# 32a4u.net
KiCad netlist of a schematic drawn in EAGLE
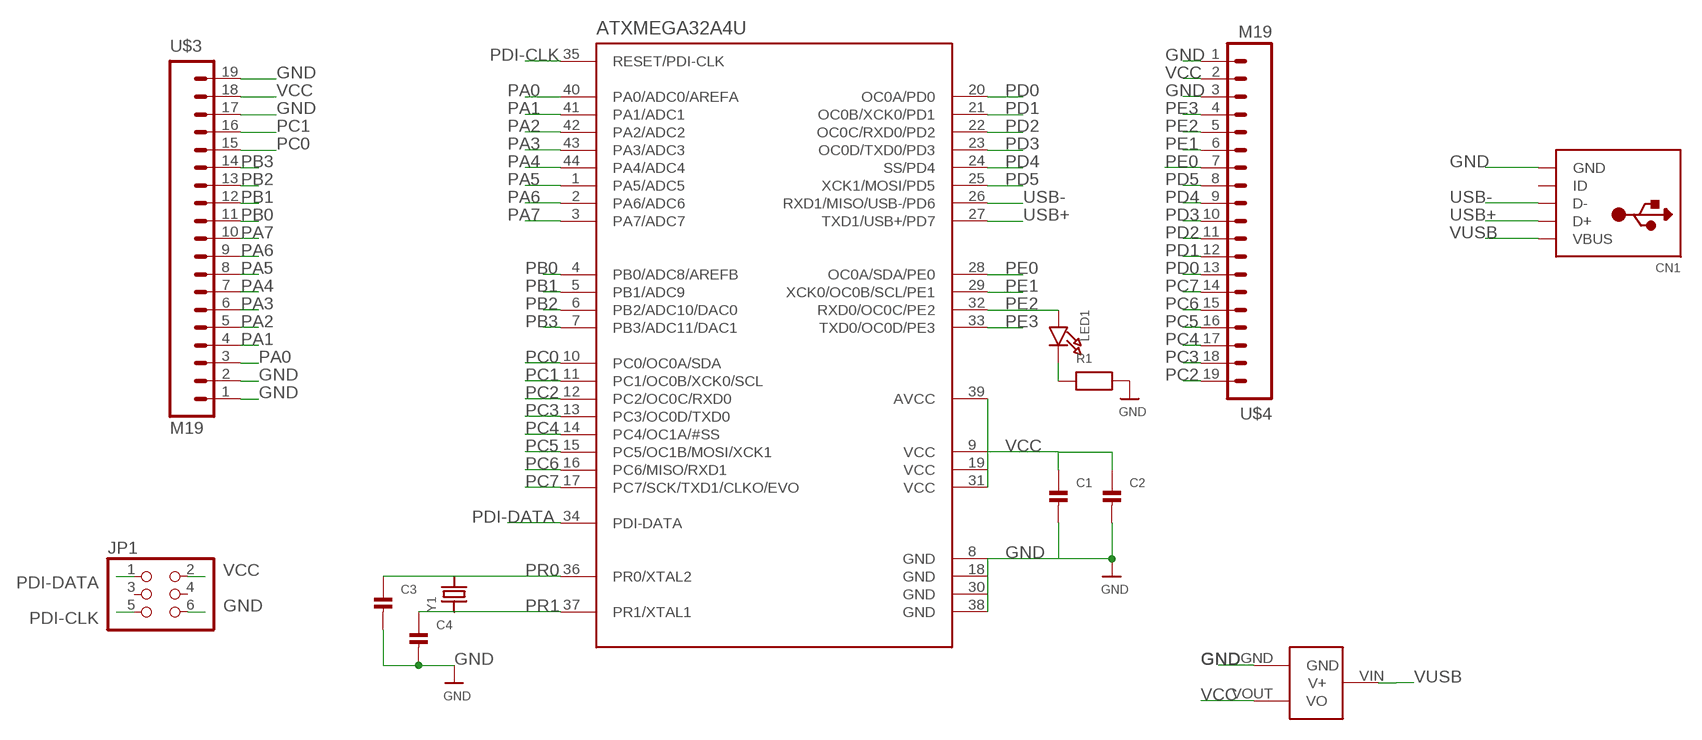
[diagram p0: schematic, sheet 1]

(export (version "E")
  (design (tool "Eeschema 10.0.6"))
  (components
    (comp (ref "ATXMEGA32A4U")
      (value "ATXMEGAXXA4U-AU")
      (footprint "eagle-import:TQFP-44")
      (libsource (lib "eagle-import") (part "ATXMEGAXXA4U-AU"))
    )
    (comp (ref "C1")
      (value "CAP_CERAMIC0603")
      (footprint "eagle-import:0603")
      (libsource (lib "eagle-import") (part "CAP_CERAMIC0603"))
    )
    (comp (ref "C2")
      (value "CAP_CERAMIC0603")
      (footprint "eagle-import:0603")
      (libsource (lib "eagle-import") (part "CAP_CERAMIC0603"))
    )
    (comp (ref "C3")
      (value "CAP_CERAMIC0603")
      (footprint "eagle-import:0603")
      (libsource (lib "eagle-import") (part "CAP_CERAMIC0603"))
    )
    (comp (ref "C4")
      (value "CAP_CERAMIC0603")
      (footprint "eagle-import:0603")
      (libsource (lib "eagle-import") (part "CAP_CERAMIC0603"))
    )
    (comp (ref "CN1")
      (value "USBMICROB")
      (footprint "eagle-import:USB-MICROB")
      (libsource (lib "eagle-import") (part "USBMICROB"))
    )
    (comp (ref "JP1")
      (value "HEADER-2X3")
      (footprint "eagle-import:2X03")
      (libsource (lib "eagle-import") (part "HEADER-2X3"))
    )
    (comp (ref "LED1")
      (value "LED0603")
      (footprint "eagle-import:CHIPLED_0603")
      (libsource (lib "eagle-import") (part "LED0603"))
    )
    (comp (ref "R1")
      (value "RESISTOR0603")
      (footprint "eagle-import:0603")
      (libsource (lib "eagle-import") (part "RESISTOR0603"))
    )
    (comp (ref "U$2")
      (value "MCP1700")
      (footprint "eagle-import:SOT23-3")
      (libsource (lib "eagle-import") (part "MCP1700"))
    )
    (comp (ref "U$3")
      (value "M19")
      (footprint "eagle-import:1X19")
      (libsource (lib "eagle-import") (part "M19"))
    )
    (comp (ref "U$4")
      (value "M19")
      (footprint "eagle-import:1X19")
      (libsource (lib "eagle-import") (part "M19"))
    )
    (comp (ref "Y1")
      (value "CRYSTAL")
      (footprint "eagle-import:NX8045GB")
      (libsource (lib "eagle-import") (part "CRYSTAL"))
    )
  )
  (nets
    (net (code "1") (name "/PA0") (class "Default")
      (node (ref "ATXMEGA32A4U") (pin "40") (pinfunction "PA0/ADC0/AREFA_40") (pintype "bidirectional"))
      (node (ref "U$3") (pin "3") (pinfunction "3_3") (pintype "passive"))
    )
    (net (code "2") (name "/PA1") (class "Default")
      (node (ref "ATXMEGA32A4U") (pin "41") (pinfunction "PA1/ADC1_41") (pintype "bidirectional"))
      (node (ref "U$3") (pin "4") (pinfunction "4_4") (pintype "passive"))
    )
    (net (code "3") (name "/PA2") (class "Default")
      (node (ref "ATXMEGA32A4U") (pin "42") (pinfunction "PA2/ADC2_42") (pintype "bidirectional"))
      (node (ref "U$3") (pin "5") (pinfunction "5_5") (pintype "passive"))
    )
    (net (code "4") (name "/PA3") (class "Default")
      (node (ref "ATXMEGA32A4U") (pin "43") (pinfunction "PA3/ADC3_43") (pintype "bidirectional"))
      (node (ref "U$3") (pin "6") (pinfunction "6_6") (pintype "passive"))
    )
    (net (code "5") (name "/PA4") (class "Default")
      (node (ref "ATXMEGA32A4U") (pin "44") (pinfunction "PA4/ADC4_44") (pintype "bidirectional"))
      (node (ref "U$3") (pin "7") (pinfunction "7_7") (pintype "passive"))
    )
    (net (code "6") (name "/PA5") (class "Default")
      (node (ref "ATXMEGA32A4U") (pin "1") (pinfunction "PA5/ADC5_1") (pintype "bidirectional"))
      (node (ref "U$3") (pin "8") (pinfunction "8_8") (pintype "passive"))
    )
    (net (code "7") (name "/PA6") (class "Default")
      (node (ref "ATXMEGA32A4U") (pin "2") (pinfunction "PA6/ADC6_2") (pintype "bidirectional"))
      (node (ref "U$3") (pin "9") (pinfunction "9_9") (pintype "passive"))
    )
    (net (code "8") (name "/PA7") (class "Default")
      (node (ref "ATXMEGA32A4U") (pin "3") (pinfunction "PA7/ADC7_3") (pintype "bidirectional"))
      (node (ref "U$3") (pin "10") (pinfunction "10_10") (pintype "passive"))
    )
    (net (code "9") (name "/PB0") (class "Default")
      (node (ref "ATXMEGA32A4U") (pin "4") (pinfunction "PB0/ADC8/AREFB_4") (pintype "bidirectional"))
      (node (ref "U$3") (pin "11") (pinfunction "11_11") (pintype "passive"))
    )
    (net (code "10") (name "/PB1") (class "Default")
      (node (ref "ATXMEGA32A4U") (pin "5") (pinfunction "PB1/ADC9_5") (pintype "bidirectional"))
      (node (ref "U$3") (pin "12") (pinfunction "12_12") (pintype "passive"))
    )
    (net (code "11") (name "/PB2") (class "Default")
      (node (ref "ATXMEGA32A4U") (pin "6") (pinfunction "PB2/ADC10/DAC0_6") (pintype "bidirectional"))
      (node (ref "U$3") (pin "13") (pinfunction "13_13") (pintype "passive"))
    )
    (net (code "12") (name "/PB3") (class "Default")
      (node (ref "ATXMEGA32A4U") (pin "7") (pinfunction "PB3/ADC11/DAC1_7") (pintype "bidirectional"))
      (node (ref "U$3") (pin "14") (pinfunction "14_14") (pintype "passive"))
    )
    (net (code "13") (name "/PC0") (class "Default")
      (node (ref "ATXMEGA32A4U") (pin "10") (pinfunction "PC0/OC0A/SDA_10") (pintype "bidirectional"))
      (node (ref "U$3") (pin "15") (pinfunction "15_15") (pintype "passive"))
    )
    (net (code "14") (name "/PC1") (class "Default")
      (node (ref "ATXMEGA32A4U") (pin "11") (pinfunction "PC1/OC0B/XCK0/SCL_11") (pintype "bidirectional"))
      (node (ref "U$3") (pin "16") (pinfunction "16_16") (pintype "passive"))
    )
    (net (code "15") (name "/PC2") (class "Default")
      (node (ref "ATXMEGA32A4U") (pin "12") (pinfunction "PC2/OC0C/RXD0_12") (pintype "bidirectional"))
      (node (ref "U$4") (pin "19") (pinfunction "19_19") (pintype "passive"))
    )
    (net (code "16") (name "/PC3") (class "Default")
      (node (ref "ATXMEGA32A4U") (pin "13") (pinfunction "PC3/OC0D/TXD0_13") (pintype "bidirectional"))
      (node (ref "U$4") (pin "18") (pinfunction "18_18") (pintype "passive"))
    )
    (net (code "17") (name "/PC4") (class "Default")
      (node (ref "ATXMEGA32A4U") (pin "14") (pinfunction "PC4/OC1A/#SS_14") (pintype "bidirectional"))
      (node (ref "U$4") (pin "17") (pinfunction "17_17") (pintype "passive"))
    )
    (net (code "18") (name "/PC5") (class "Default")
      (node (ref "ATXMEGA32A4U") (pin "15") (pinfunction "PC5/OC1B/MOSI/XCK1_15") (pintype "bidirectional"))
      (node (ref "U$4") (pin "16") (pinfunction "16_16") (pintype "passive"))
    )
    (net (code "19") (name "/PC6") (class "Default")
      (node (ref "ATXMEGA32A4U") (pin "16") (pinfunction "PC6/MISO/RXD1_16") (pintype "bidirectional"))
      (node (ref "U$4") (pin "15") (pinfunction "15_15") (pintype "passive"))
    )
    (net (code "20") (name "/PC7") (class "Default")
      (node (ref "ATXMEGA32A4U") (pin "17") (pinfunction "PC7/SCK/TXD1/CLKO/EVO_17") (pintype "bidirectional"))
      (node (ref "U$4") (pin "14") (pinfunction "14_14") (pintype "passive"))
    )
    (net (code "21") (name "/PD0") (class "Default")
      (node (ref "ATXMEGA32A4U") (pin "20") (pinfunction "OC0A/PD0_20") (pintype "bidirectional"))
      (node (ref "U$4") (pin "13") (pinfunction "13_13") (pintype "passive"))
    )
    (net (code "22") (name "/PD1") (class "Default")
      (node (ref "ATXMEGA32A4U") (pin "21") (pinfunction "OC0B/XCK0/PD1_21") (pintype "bidirectional"))
      (node (ref "U$4") (pin "12") (pinfunction "12_12") (pintype "passive"))
    )
    (net (code "23") (name "/PD2") (class "Default")
      (node (ref "ATXMEGA32A4U") (pin "22") (pinfunction "OC0C/RXD0/PD2_22") (pintype "bidirectional"))
      (node (ref "U$4") (pin "11") (pinfunction "11_11") (pintype "passive"))
    )
    (net (code "24") (name "/PD3") (class "Default")
      (node (ref "ATXMEGA32A4U") (pin "23") (pinfunction "OC0D/TXD0/PD3_23") (pintype "bidirectional"))
      (node (ref "U$4") (pin "10") (pinfunction "10_10") (pintype "passive"))
    )
    (net (code "25") (name "/PD4") (class "Default")
      (node (ref "ATXMEGA32A4U") (pin "24") (pinfunction "SS/PD4_24") (pintype "bidirectional"))
      (node (ref "U$4") (pin "9") (pinfunction "9_9") (pintype "passive"))
    )
    (net (code "26") (name "/PD5") (class "Default")
      (node (ref "ATXMEGA32A4U") (pin "25") (pinfunction "XCK1/MOSI/PD5_25") (pintype "bidirectional"))
      (node (ref "U$4") (pin "8") (pinfunction "8_8") (pintype "passive"))
    )
    (net (code "27") (name "/PDI-CLK") (class "Default")
      (node (ref "ATXMEGA32A4U") (pin "35") (pinfunction "RESET/PDI-CLK_35") (pintype "input"))
      (node (ref "JP1") (pin "5") (pinfunction "5_5") (pintype "passive"))
    )
    (net (code "28") (name "/PDI-DATA") (class "Default")
      (node (ref "ATXMEGA32A4U") (pin "34") (pinfunction "PDI-DATA_34") (pintype "bidirectional"))
      (node (ref "JP1") (pin "1") (pinfunction "1_1") (pintype "passive"))
    )
    (net (code "29") (name "/PE0") (class "Default")
      (node (ref "ATXMEGA32A4U") (pin "28") (pinfunction "OC0A/SDA/PE0_28") (pintype "bidirectional"))
      (node (ref "U$4") (pin "7") (pinfunction "7_7") (pintype "passive"))
    )
    (net (code "30") (name "/PE1") (class "Default")
      (node (ref "ATXMEGA32A4U") (pin "29") (pinfunction "XCK0/OC0B/SCL/PE1_29") (pintype "bidirectional"))
      (node (ref "U$4") (pin "6") (pinfunction "6_6") (pintype "passive"))
    )
    (net (code "31") (name "/PE2") (class "Default")
      (node (ref "ATXMEGA32A4U") (pin "32") (pinfunction "RXD0/OC0C/PE2_32") (pintype "bidirectional"))
      (node (ref "LED1") (pin "A") (pinfunction "A_A") (pintype "passive"))
      (node (ref "U$4") (pin "5") (pinfunction "5_5") (pintype "passive"))
    )
    (net (code "32") (name "/PE3") (class "Default")
      (node (ref "ATXMEGA32A4U") (pin "33") (pinfunction "TXD0/OC0D/PE3_33") (pintype "bidirectional"))
      (node (ref "U$4") (pin "4") (pinfunction "4_4") (pintype "passive"))
    )
    (net (code "33") (name "/PR0") (class "Default")
      (node (ref "ATXMEGA32A4U") (pin "36") (pinfunction "PR0/XTAL2_36") (pintype "bidirectional"))
      (node (ref "C3") (pin "1") (pinfunction "P$1_1") (pintype "passive"))
      (node (ref "Y1") (pin "P$2") (pinfunction "2_P$2") (pintype "passive"))
    )
    (net (code "34") (name "/PR1") (class "Default")
      (node (ref "ATXMEGA32A4U") (pin "37") (pinfunction "PR1/XTAL1_37") (pintype "bidirectional"))
      (node (ref "C4") (pin "1") (pinfunction "P$1_1") (pintype "passive"))
      (node (ref "Y1") (pin "P$1") (pinfunction "1_P$1") (pintype "passive"))
    )
    (net (code "35") (name "/USB+") (class "Default")
      (node (ref "ATXMEGA32A4U") (pin "27") (pinfunction "TXD1/USB+/PD7_27") (pintype "bidirectional"))
      (node (ref "CN1") (pin "P3") (pinfunction "D+_P3") (pintype "bidirectional"))
    )
    (net (code "36") (name "/USB-") (class "Default")
      (node (ref "ATXMEGA32A4U") (pin "26") (pinfunction "RXD1/MISO/USB-/PD6_26") (pintype "bidirectional"))
      (node (ref "CN1") (pin "P2") (pinfunction "D-_P2") (pintype "bidirectional"))
    )
    (net (code "37") (name "/VCC") (class "Default")
      (node (ref "ATXMEGA32A4U") (pin "19") (pinfunction "VCC_19") (pintype "power_in"))
      (node (ref "ATXMEGA32A4U") (pin "31") (pinfunction "VCC_31") (pintype "power_in"))
      (node (ref "ATXMEGA32A4U") (pin "39") (pinfunction "AVCC_39") (pintype "power_in"))
      (node (ref "ATXMEGA32A4U") (pin "9") (pinfunction "VCC_9") (pintype "power_in"))
      (node (ref "C1") (pin "1") (pinfunction "P$1_1") (pintype "passive"))
      (node (ref "C2") (pin "1") (pinfunction "P$1_1") (pintype "passive"))
      (node (ref "JP1") (pin "2") (pinfunction "2_2") (pintype "passive"))
      (node (ref "U$2") (pin "VOUT") (pinfunction "VO_VOUT") (pintype "bidirectional"))
      (node (ref "U$3") (pin "18") (pinfunction "18_18") (pintype "passive"))
      (node (ref "U$4") (pin "2") (pinfunction "2_2") (pintype "passive"))
    )
    (net (code "38") (name "/VUSB") (class "Default")
      (node (ref "CN1") (pin "P1") (pinfunction "VBUS_P1") (pintype "power_in"))
      (node (ref "U$2") (pin "VIN") (pinfunction "V+_VIN") (pintype "bidirectional"))
    )
    (net (code "39") (name "GND") (class "Default")
      (node (ref "ATXMEGA32A4U") (pin "18") (pinfunction "GND_18") (pintype "power_in"))
      (node (ref "ATXMEGA32A4U") (pin "30") (pinfunction "GND_30") (pintype "power_in"))
      (node (ref "ATXMEGA32A4U") (pin "38") (pinfunction "GND_38") (pintype "power_in"))
      (node (ref "ATXMEGA32A4U") (pin "8") (pinfunction "GND_8") (pintype "power_in"))
      (node (ref "C1") (pin "2") (pinfunction "P$2_2") (pintype "passive"))
      (node (ref "C2") (pin "2") (pinfunction "P$2_2") (pintype "passive"))
      (node (ref "C3") (pin "2") (pinfunction "P$2_2") (pintype "passive"))
      (node (ref "C4") (pin "2") (pinfunction "P$2_2") (pintype "passive"))
      (node (ref "CN1") (pin "P5") (pinfunction "GND_P5") (pintype "power_in"))
      (node (ref "JP1") (pin "6") (pinfunction "6_6") (pintype "passive"))
      (node (ref "R1") (pin "2") (pinfunction "2_2") (pintype "passive"))
      (node (ref "U$2") (pin "GND") (pinfunction "GND_GND") (pintype "bidirectional"))
      (node (ref "U$3") (pin "1") (pinfunction "1_1") (pintype "passive"))
      (node (ref "U$3") (pin "17") (pinfunction "17_17") (pintype "passive"))
      (node (ref "U$3") (pin "19") (pinfunction "19_19") (pintype "passive"))
      (node (ref "U$3") (pin "2") (pinfunction "2_2") (pintype "passive"))
      (node (ref "U$4") (pin "1") (pinfunction "1_1") (pintype "passive"))
      (node (ref "U$4") (pin "3") (pinfunction "3_3") (pintype "passive"))
    )
    (net (code "40") (name "Net-(LED1-PadC)") (class "Default")
      (node (ref "LED1") (pin "C") (pinfunction "C_C") (pintype "passive"))
      (node (ref "R1") (pin "1") (pinfunction "1_1") (pintype "passive"))
    )
    (net (code "41") (name "unconnected-(CN1-ID-PadP4)") (class "Default")
      (node (ref "CN1") (pin "P4") (pinfunction "ID_P4") (pintype "bidirectional"))
    )
    (net (code "42") (name "unconnected-(JP1-Pad3)") (class "Default")
      (node (ref "JP1") (pin "3") (pinfunction "3_3") (pintype "passive"))
    )
    (net (code "43") (name "unconnected-(JP1-Pad4)") (class "Default")
      (node (ref "JP1") (pin "4") (pinfunction "4_4") (pintype "passive"))
    )
  )
)
